# charlyplex_badge.net
KiCad netlist of a schematic drawn in EAGLE
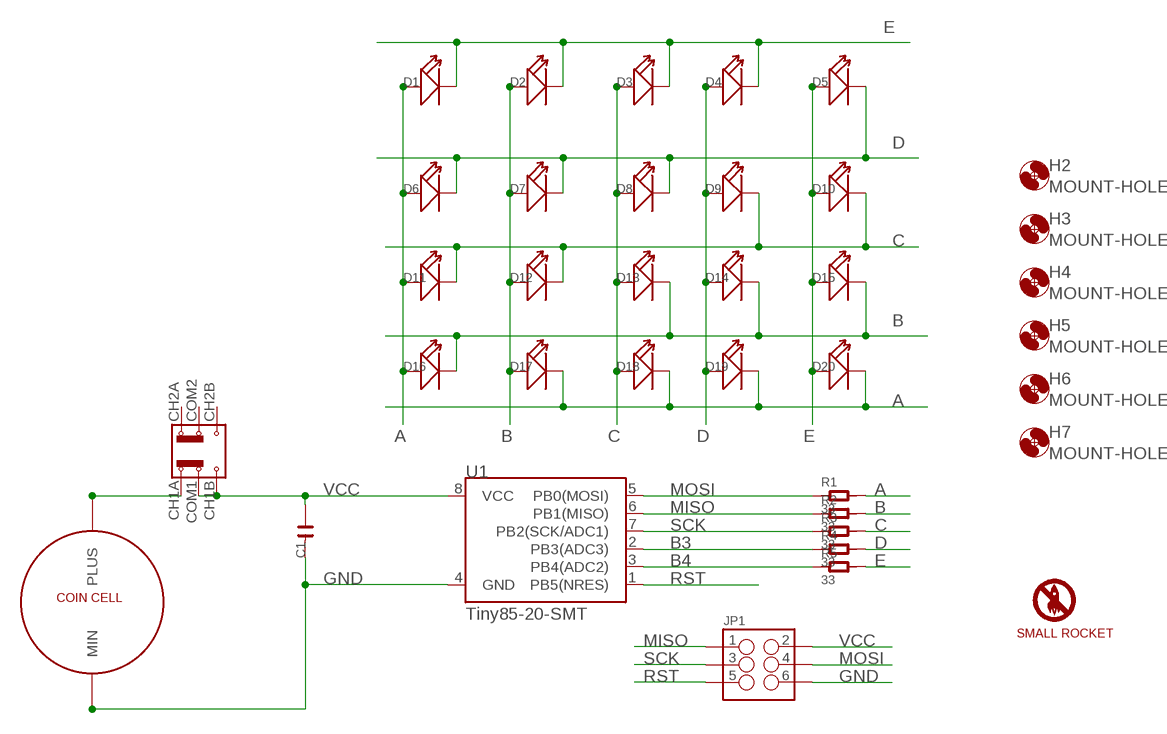
[diagram p0: schematic, sheet 1]

(export (version "E")
  (design (tool "Eeschema 10.0.6"))
  (components
    (comp (ref "C1")
      (value "C-0603")
      (footprint "eagle-import:C0603")
      (libsource (lib "eagle-import") (part "C-0603"))
    )
    (comp (ref "D1")
      (value "LED")
      (footprint "eagle-import:LED0603")
      (libsource (lib "eagle-import") (part "LED"))
    )
    (comp (ref "D2")
      (value "LED")
      (footprint "eagle-import:LED0603")
      (libsource (lib "eagle-import") (part "LED"))
    )
    (comp (ref "D3")
      (value "LED")
      (footprint "eagle-import:LED0603")
      (libsource (lib "eagle-import") (part "LED"))
    )
    (comp (ref "D4")
      (value "LED")
      (footprint "eagle-import:LED0603")
      (libsource (lib "eagle-import") (part "LED"))
    )
    (comp (ref "D5")
      (value "LED")
      (footprint "eagle-import:LED0603")
      (libsource (lib "eagle-import") (part "LED"))
    )
    (comp (ref "D6")
      (value "LED")
      (footprint "eagle-import:LED0603")
      (libsource (lib "eagle-import") (part "LED"))
    )
    (comp (ref "D7")
      (value "LED")
      (footprint "eagle-import:LED0603")
      (libsource (lib "eagle-import") (part "LED"))
    )
    (comp (ref "D8")
      (value "LED")
      (footprint "eagle-import:LED0603")
      (libsource (lib "eagle-import") (part "LED"))
    )
    (comp (ref "D9")
      (value "LED")
      (footprint "eagle-import:LED0603")
      (libsource (lib "eagle-import") (part "LED"))
    )
    (comp (ref "D10")
      (value "LED")
      (footprint "eagle-import:LED0603")
      (libsource (lib "eagle-import") (part "LED"))
    )
    (comp (ref "D11")
      (value "LED")
      (footprint "eagle-import:LED0603")
      (libsource (lib "eagle-import") (part "LED"))
    )
    (comp (ref "D12")
      (value "LED")
      (footprint "eagle-import:LED0603")
      (libsource (lib "eagle-import") (part "LED"))
    )
    (comp (ref "D13")
      (value "LED")
      (footprint "eagle-import:LED0603")
      (libsource (lib "eagle-import") (part "LED"))
    )
    (comp (ref "D14")
      (value "LED")
      (footprint "eagle-import:LED0603")
      (libsource (lib "eagle-import") (part "LED"))
    )
    (comp (ref "D15")
      (value "LED")
      (footprint "eagle-import:LED0603")
      (libsource (lib "eagle-import") (part "LED"))
    )
    (comp (ref "D16")
      (value "LED")
      (footprint "eagle-import:LED0603")
      (libsource (lib "eagle-import") (part "LED"))
    )
    (comp (ref "D17")
      (value "LED")
      (footprint "eagle-import:LED0603")
      (libsource (lib "eagle-import") (part "LED"))
    )
    (comp (ref "D18")
      (value "LED")
      (footprint "eagle-import:LED0603")
      (libsource (lib "eagle-import") (part "LED"))
    )
    (comp (ref "D19")
      (value "LED")
      (footprint "eagle-import:LED0603")
      (libsource (lib "eagle-import") (part "LED"))
    )
    (comp (ref "D20")
      (value "LED")
      (footprint "eagle-import:LED0603")
      (libsource (lib "eagle-import") (part "LED"))
    )
    (comp (ref "H2")
      (value "MOUNT-HOLE")
      (footprint "eagle-import:3.2-NOMARKINGS-SMALLSAFEZONE")
      (libsource (lib "eagle-import") (part "MOUNT-HOLE"))
    )
    (comp (ref "H3")
      (value "MOUNT-HOLE")
      (footprint "eagle-import:3.2-NOMARKINGS-SMALLSAFEZONE")
      (libsource (lib "eagle-import") (part "MOUNT-HOLE"))
    )
    (comp (ref "H4")
      (value "MOUNT-HOLE")
      (footprint "eagle-import:3.2-NOMARKINGS-SMALLSAFEZONE")
      (libsource (lib "eagle-import") (part "MOUNT-HOLE"))
    )
    (comp (ref "H5")
      (value "MOUNT-HOLE")
      (footprint "eagle-import:3.2-NOMARKINGS-SMALLSAFEZONE")
      (libsource (lib "eagle-import") (part "MOUNT-HOLE"))
    )
    (comp (ref "H6")
      (value "MOUNT-HOLE")
      (footprint "eagle-import:3.2-NOMARKINGS-SMALLSAFEZONE")
      (libsource (lib "eagle-import") (part "MOUNT-HOLE"))
    )
    (comp (ref "H7")
      (value "MOUNT-HOLE")
      (footprint "eagle-import:3.2-NOMARKINGS-SMALLSAFEZONE")
      (libsource (lib "eagle-import") (part "MOUNT-HOLE"))
    )
    (comp (ref "JP1")
      (value "M03X2SMT")
      (footprint "eagle-import:2X3_SMT_POSTS")
      (libsource (lib "eagle-import") (part "M03X2SMT"))
    )
    (comp (ref "R1")
      (value "33")
      (footprint "eagle-import:R0603")
      (libsource (lib "eagle-import") (part "R-0603"))
    )
    (comp (ref "R2")
      (value "33")
      (footprint "eagle-import:R0603")
      (libsource (lib "eagle-import") (part "R-0603"))
    )
    (comp (ref "R3")
      (value "33")
      (footprint "eagle-import:R0603")
      (libsource (lib "eagle-import") (part "R-0603"))
    )
    (comp (ref "R4")
      (value "33")
      (footprint "eagle-import:R0603")
      (libsource (lib "eagle-import") (part "R-0603"))
    )
    (comp (ref "R5")
      (value "33")
      (footprint "eagle-import:R0603")
      (libsource (lib "eagle-import") (part "R-0603"))
    )
    (comp (ref "SW1")
      (value "SWITCH-2CH-6P-3010010P1")
      (footprint "eagle-import:6P-2CH-2.54-9.1X3.5X3.2+2H")
      (libsource (lib "eagle-import") (part "SWITCH-2CH-6P-3010010P1"))
    )
    (comp (ref "U$1")
      (value "COINCELL")
      (footprint "eagle-import:2032HOLDER-SZ")
      (libsource (lib "eagle-import") (part "COINCELL"))
    )
    (comp (ref "U$2")
      (value "SMALLROCKET")
      (footprint "eagle-import:SMALLROCKET")
      (libsource (lib "eagle-import") (part "SMALLROCKET"))
    )
    (comp (ref "U1")
      (value "Tiny85-20-SMT")
      (footprint "eagle-import:SO08-EIAJ")
      (libsource (lib "eagle-import") (part "ATTINY45TINY85-20-SMT"))
    )
  )
  (nets
    (net (code "1") (name "/A") (class "Default")
      (node (ref "D1") (pin "+") (pinfunction "+_+") (pintype "passive"))
      (node (ref "D11") (pin "+") (pinfunction "+_+") (pintype "passive"))
      (node (ref "D16") (pin "+") (pinfunction "+_+") (pintype "passive"))
      (node (ref "D17") (pin "-") (pinfunction "-_-") (pintype "passive"))
      (node (ref "D18") (pin "-") (pinfunction "-_-") (pintype "passive"))
      (node (ref "D19") (pin "-") (pinfunction "-_-") (pintype "passive"))
      (node (ref "D20") (pin "-") (pinfunction "-_-") (pintype "passive"))
      (node (ref "D6") (pin "+") (pinfunction "+_+") (pintype "passive"))
      (node (ref "R1") (pin "2") (pinfunction "2_2") (pintype "bidirectional"))
    )
    (net (code "2") (name "/B") (class "Default")
      (node (ref "D12") (pin "+") (pinfunction "+_+") (pintype "passive"))
      (node (ref "D13") (pin "-") (pinfunction "-_-") (pintype "passive"))
      (node (ref "D14") (pin "-") (pinfunction "-_-") (pintype "passive"))
      (node (ref "D15") (pin "-") (pinfunction "-_-") (pintype "passive"))
      (node (ref "D16") (pin "-") (pinfunction "-_-") (pintype "passive"))
      (node (ref "D17") (pin "+") (pinfunction "+_+") (pintype "passive"))
      (node (ref "D2") (pin "+") (pinfunction "+_+") (pintype "passive"))
      (node (ref "D7") (pin "+") (pinfunction "+_+") (pintype "passive"))
      (node (ref "R2") (pin "2") (pinfunction "2_2") (pintype "bidirectional"))
    )
    (net (code "3") (name "/B3") (class "Default")
      (node (ref "R4") (pin "1") (pinfunction "1_1") (pintype "bidirectional"))
      (node (ref "U1") (pin "2") (pinfunction "PB3(ADC3)_2") (pintype "bidirectional"))
    )
    (net (code "4") (name "/B4") (class "Default")
      (node (ref "R5") (pin "1") (pinfunction "1_1") (pintype "bidirectional"))
      (node (ref "U1") (pin "3") (pinfunction "PB4(ADC2)_3") (pintype "bidirectional"))
    )
    (net (code "5") (name "/C") (class "Default")
      (node (ref "D10") (pin "-") (pinfunction "-_-") (pintype "passive"))
      (node (ref "D11") (pin "-") (pinfunction "-_-") (pintype "passive"))
      (node (ref "D12") (pin "-") (pinfunction "-_-") (pintype "passive"))
      (node (ref "D13") (pin "+") (pinfunction "+_+") (pintype "passive"))
      (node (ref "D18") (pin "+") (pinfunction "+_+") (pintype "passive"))
      (node (ref "D3") (pin "+") (pinfunction "+_+") (pintype "passive"))
      (node (ref "D8") (pin "+") (pinfunction "+_+") (pintype "passive"))
      (node (ref "D9") (pin "-") (pinfunction "-_-") (pintype "passive"))
      (node (ref "R3") (pin "2") (pinfunction "2_2") (pintype "bidirectional"))
    )
    (net (code "6") (name "/D") (class "Default")
      (node (ref "D14") (pin "+") (pinfunction "+_+") (pintype "passive"))
      (node (ref "D19") (pin "+") (pinfunction "+_+") (pintype "passive"))
      (node (ref "D4") (pin "+") (pinfunction "+_+") (pintype "passive"))
      (node (ref "D5") (pin "-") (pinfunction "-_-") (pintype "passive"))
      (node (ref "D6") (pin "-") (pinfunction "-_-") (pintype "passive"))
      (node (ref "D7") (pin "-") (pinfunction "-_-") (pintype "passive"))
      (node (ref "D8") (pin "-") (pinfunction "-_-") (pintype "passive"))
      (node (ref "D9") (pin "+") (pinfunction "+_+") (pintype "passive"))
      (node (ref "R4") (pin "2") (pinfunction "2_2") (pintype "bidirectional"))
    )
    (net (code "7") (name "/E") (class "Default")
      (node (ref "D1") (pin "-") (pinfunction "-_-") (pintype "passive"))
      (node (ref "D10") (pin "+") (pinfunction "+_+") (pintype "passive"))
      (node (ref "D15") (pin "+") (pinfunction "+_+") (pintype "passive"))
      (node (ref "D2") (pin "-") (pinfunction "-_-") (pintype "passive"))
      (node (ref "D20") (pin "+") (pinfunction "+_+") (pintype "passive"))
      (node (ref "D3") (pin "-") (pinfunction "-_-") (pintype "passive"))
      (node (ref "D4") (pin "-") (pinfunction "-_-") (pintype "passive"))
      (node (ref "D5") (pin "+") (pinfunction "+_+") (pintype "passive"))
      (node (ref "R5") (pin "2") (pinfunction "2_2") (pintype "bidirectional"))
    )
    (net (code "8") (name "/GND") (class "Default")
      (node (ref "C1") (pin "1") (pinfunction "1_1") (pintype "bidirectional"))
      (node (ref "JP1") (pin "6") (pinfunction "6_6") (pintype "bidirectional"))
      (node (ref "U$1") (pin "MIN") (pinfunction "MIN_MIN") (pintype "bidirectional"))
      (node (ref "U1") (pin "4") (pinfunction "GND_4") (pintype "bidirectional"))
    )
    (net (code "9") (name "/MISO") (class "Default")
      (node (ref "JP1") (pin "1") (pinfunction "1_1") (pintype "bidirectional"))
      (node (ref "R2") (pin "1") (pinfunction "1_1") (pintype "bidirectional"))
      (node (ref "U1") (pin "6") (pinfunction "PB1(MISO)_6") (pintype "bidirectional"))
    )
    (net (code "10") (name "/MOSI") (class "Default")
      (node (ref "JP1") (pin "4") (pinfunction "4_4") (pintype "bidirectional"))
      (node (ref "R1") (pin "1") (pinfunction "1_1") (pintype "bidirectional"))
      (node (ref "U1") (pin "5") (pinfunction "PB0(MOSI)_5") (pintype "bidirectional"))
    )
    (net (code "11") (name "/RST") (class "Default")
      (node (ref "JP1") (pin "5") (pinfunction "5_5") (pintype "bidirectional"))
      (node (ref "U1") (pin "1") (pinfunction "PB5(NRES)_1") (pintype "bidirectional"))
    )
    (net (code "12") (name "/SCK") (class "Default")
      (node (ref "JP1") (pin "3") (pinfunction "3_3") (pintype "bidirectional"))
      (node (ref "R3") (pin "1") (pinfunction "1_1") (pintype "bidirectional"))
      (node (ref "U1") (pin "7") (pinfunction "PB2(SCK/ADC1)_7") (pintype "bidirectional"))
    )
    (net (code "13") (name "/VCC") (class "Default")
      (node (ref "C1") (pin "2") (pinfunction "2_2") (pintype "bidirectional"))
      (node (ref "JP1") (pin "2") (pinfunction "2_2") (pintype "bidirectional"))
      (node (ref "SW1") (pin "CH1B") (pinfunction "CH1B_CH1B") (pintype "bidirectional"))
      (node (ref "SW1") (pin "COM1") (pinfunction "COM1_COM1") (pintype "bidirectional"))
      (node (ref "U1") (pin "8") (pinfunction "VCC_8") (pintype "bidirectional"))
    )
    (net (code "14") (name "Net-(SW1-PadCH1A)") (class "Default")
      (node (ref "SW1") (pin "CH1A") (pinfunction "CH1A_CH1A") (pintype "bidirectional"))
      (node (ref "U$1") (pin "PLUS") (pinfunction "PLUS_PLUS") (pintype "bidirectional"))
    )
    (net (code "15") (name "unconnected-(SW1-PadCH2A)") (class "Default")
      (node (ref "SW1") (pin "CH2A") (pinfunction "CH2A_CH2A") (pintype "bidirectional"))
    )
    (net (code "16") (name "unconnected-(SW1-PadCH2B)") (class "Default")
      (node (ref "SW1") (pin "CH2B") (pinfunction "CH2B_CH2B") (pintype "bidirectional"))
    )
    (net (code "17") (name "unconnected-(SW1-PadCOM2)") (class "Default")
      (node (ref "SW1") (pin "COM2") (pinfunction "COM2_COM2") (pintype "bidirectional"))
    )
  )
)
